# DC_DC.net
KiCad netlist of a schematic drawn in Altium Designer
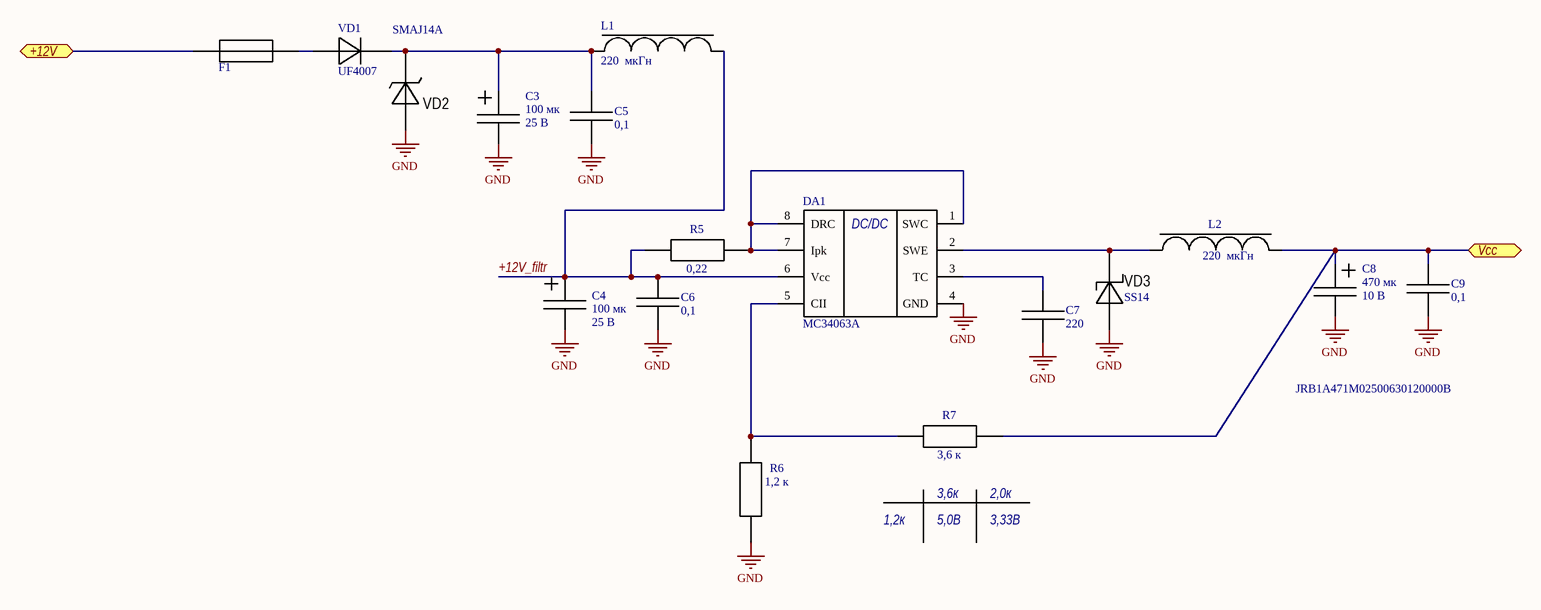
[diagram p0: DC_DC.SchDoc]

(export (version "E")
  (design (tool "Eeschema 10.0.6"))
  (components
    (comp (ref "C3")
      (value "~")
      (footprint "K50-35_6.3mm")
      (fields
        (field (name "PART NUMBER") "Конденсатор электролит. K50-35 100 мкФ 25 В +/- 20% JRB1E101M02500630110000B \"JB\"")
        (field (name "MANUFACTURER") "\"JB\"")
        (field (name "MANUFACTURERPARTNUMBER") "JRB1E101M02500630110000B")
        (field (name "POWER/VOLTAGE") "25 В")
        (field (name "VALUE SCH") "100 мк")
      )
      (libsource (lib "Library") (part "Конденсаторы электролитические"))
    )
    (comp (ref "C4")
      (value "~")
      (footprint "K50-35_6.3mm")
      (fields
        (field (name "PART NUMBER") "Конденсатор электролит. K50-35 100 мкФ 25 В +/- 20% JRB1E101M02500630110000B \"JB\"")
        (field (name "MANUFACTURER") "\"JB\"")
        (field (name "MANUFACTURERPARTNUMBER") "JRB1E101M02500630110000B")
        (field (name "POWER/VOLTAGE") "25 В")
        (field (name "VALUE SCH") "100 мк")
      )
      (libsource (lib "Library") (part "Конденсаторы электролитические"))
    )
    (comp (ref "C5")
      (value "Конденсаторы керамические")
      (footprint "C0603_autoMount")
      (fields
        (field (name "PART NUMBER") "Чип. керам. 0603 0,1 мкФ 50 В +/-10% X7R CC0603KKX7R9BB104 \"Yageo\"")
        (field (name "MANUFACTURER") "\"Yageo\"")
        (field (name "MANUFACTURERPARTNUMBER") "CC0603KKX7R9BB104")
        (field (name "VALUE SCH") "0,1")
      )
      (libsource (lib "Library") (part "Конденсаторы керамические"))
    )
    (comp (ref "C6")
      (value "Конденсаторы керамические")
      (footprint "C0603_autoMount")
      (fields
        (field (name "PART NUMBER") "Чип. керам. 0603 0,1 мкФ 50 В +/-10% X7R CC0603KKX7R9BB104 \"Yageo\"")
        (field (name "MANUFACTURER") "\"Yageo\"")
        (field (name "MANUFACTURERPARTNUMBER") "CC0603KKX7R9BB104")
        (field (name "VALUE SCH") "0,1")
      )
      (libsource (lib "Library") (part "Конденсаторы керамические"))
    )
    (comp (ref "C7")
      (value "Конденсаторы керамические")
      (footprint "C0603_autoMount")
      (fields
        (field (name "PART NUMBER") "Чип. керам. 0603 220 пФ 50 В +/-5% NP0 GRM1885C1H221J \"Murata\"")
        (field (name "MANUFACTURER") "\"Murata\"")
        (field (name "MANUFACTURERPARTNUMBER") "GRM1885C1H221J")
        (field (name "VALUE SCH") "220")
      )
      (libsource (lib "Library") (part "Конденсаторы керамические"))
    )
    (comp (ref "C8")
      (value "Конденсаторы электролитические")
      (footprint "K50-35_8mm")
      (fields
        (field (name "PART NUMBER") "Конденсатор электролит. К50-35 470 мкФ 10 В +/- 20% JRK1A471M03500800070000B")
        (field (name "MANUFACTURERPARTNUMBER") "JRK1A471M03500800070000B")
        (field (name "POWER/VOLTAGE") "10 В")
        (field (name "TOLERANCE") "+/- 20%")
        (field (name "VALUE SCH") "470 мк")
      )
      (libsource (lib "Library") (part "Конденсаторы электролитические"))
    )
    (comp (ref "C9")
      (value "Конденсаторы керамические")
      (footprint "C0603_autoMount")
      (fields
        (field (name "PART NUMBER") "Чип. керам. 0603 0,1 мкФ 50 В +/-10% X7R CC0603KKX7R9BB104 \"Yageo\"")
        (field (name "MANUFACTURER") "\"Yageo\"")
        (field (name "MANUFACTURERPARTNUMBER") "CC0603KKX7R9BB104")
        (field (name "VALUE SCH") "0,1")
      )
      (libsource (lib "Library") (part "Конденсаторы керамические"))
    )
    (comp (ref "DA1")
      (value "MC34063A")
      (footprint "SO-8")
      (fields
        (field (name "MANUFACTURER") "\"ST Microelectronix\"")
        (field (name "MANUFACTURERPARTNUMBER") "MC34063EC")
        (field (name "PART NUMBER") "Микросхема MC34063EC \"ST Microelectronix\" SO-8")
      )
      (libsource (lib "Library") (part "MC34063A"))
    )
    (comp (ref "F1")
      (value "Fuse")
      (footprint "R1812")
      (fields
        (field (name "PART NUMBER") "Предохранитель   0,2 A, 30 В 1812L020PR \"Littelfuse\"")
        (field (name "MANUFACTURER") "\"Littelfuse\"")
        (field (name "MANUFACTURERPARTNUMBER") "1812L020PR")
      )
      (libsource (lib "Library") (part "Fuse"))
    )
    (comp (ref "L1")
      (value "220  мкГн")
      (footprint "SDR0604")
      (fields
        (field (name "MANUFACTURER") "\"Bourns\"")
        (field (name "MANUFACTURERPARTNUMBER") "SDR0604-221KL")
        (field (name "TOLERANCE") "+/-20%")
      )
      (libsource (lib "Library") (part "Drossel"))
    )
    (comp (ref "L2")
      (value "220  мкГн")
      (footprint "SDR0604")
      (fields
        (field (name "MANUFACTURER") "\"Bourns\"")
        (field (name "MANUFACTURERPARTNUMBER") "SDR0604-221KL")
        (field (name "TOLERANCE") "+/-20%")
      )
      (libsource (lib "Library") (part "Drossel"))
    )
    (comp (ref "R5")
      (value "Resistor")
      (footprint "R1206_autoMount")
      (fields
        (field (name "PART NUMBER") "Чип рез. 1206 0,22 Ом  +/-1% RC1206FR-070R22L \"Yageo\"")
        (field (name "MANUFACTURER") "\"Yageo\"")
        (field (name "MANUFACTURERPARTNUMBER") "RC1206FR-070R22L")
        (field (name "VALUE SCH") "0,22")
      )
      (libsource (lib "Library") (part "Resistor"))
    )
    (comp (ref "R6")
      (value "Resistor")
      (footprint "R0603_autoMount")
      (fields
        (field (name "PART NUMBER") "Чип рез. 0603 1,2 кОм  +/-1% RC0603FR-071K2L \"Yageo\"")
        (field (name "MANUFACTURER") "\"Yageo\"")
        (field (name "MANUFACTURERPARTNUMBER") "RC0603FR-071K2L")
        (field (name "VALUE SСH") "1,2 к")
      )
      (libsource (lib "Library") (part "Resistor"))
    )
    (comp (ref "R7")
      (value "Resistor")
      (footprint "R0603_autoMount")
      (fields
        (field (name "PART NUMBER") "Чип рез. 0603 3,6 кОм  +/-1% RC0603FR-073K6L \"Yageo\"")
        (field (name "MANUFACTURER") "\"Yageo\"")
        (field (name "MANUFACTURERPARTNUMBER") "RC0603FR-073K6L")
        (field (name "VALUE SСH") "3,6 к")
      )
      (libsource (lib "") (part "Resistor_1"))
    )
    (comp (ref "VD1")
      (value "Diode")
      (footprint "DO-41_H_10mm")
      (fields
        (field (name "PART NUMBER") "Диод UF4007 \"ST Microelectronics\" DO-41")
        (field (name "MANUFACTURER") "\"ST Microelectronics\"")
        (field (name "MANUFACTURERPARTNUMBER") "UF4007")
      )
      (libsource (lib "Library") (part "Diode"))
    )
    (comp (ref "VD2")
      (value "TVS")
      (footprint "DO-214AC SMA")
      (fields
        (field (name "PART NUMBER") "Диод SMAJ14A \"Littelfuse\" SMA/DO-214AC")
        (field (name "MANUFACTURER") "\"Littelfuse\"")
        (field (name "MANUFACTURERPARTNUMBER") "SMAJ14A")
      )
      (libsource (lib "Library") (part "TVS"))
    )
    (comp (ref "VD3")
      (value "Shottke")
      (footprint "DO-214AC_SMA")
      (fields
        (field (name "PART NUMBER") "Диод SS14 \"ON Semiconductor\" SMA/DO-214AC")
        (field (name "MANUFACTURER") "\"ON Semiconductor\"")
        (field (name "MANUFACTURERPARTNUMBER") "SS14")
      )
      (libsource (lib "Library") (part "Shottke"))
    )
  )
  (nets
    (net (code "1") (name "/+12V") (class "Default")
      (node (ref "F1") (pin "2") (pinfunction "2_2") (pintype "passive"))
    )
    (net (code "2") (name "/+12V_filtr") (class "Default")
      (node (ref "C4") (pin "1") (pinfunction "1_1") (pintype "passive"))
      (node (ref "C6") (pin "2") (pinfunction "2_2") (pintype "passive"))
      (node (ref "DA1") (pin "6") (pinfunction "Vcc_6") (pintype "passive"))
      (node (ref "L1") (pin "1") (pinfunction "1_1") (pintype "passive"))
      (node (ref "R5") (pin "2") (pinfunction "2_2") (pintype "passive"))
    )
    (net (code "3") (name "/Vcc") (class "Default")
      (node (ref "C8") (pin "1") (pinfunction "1_1") (pintype "passive"))
      (node (ref "C9") (pin "2") (pinfunction "2_2") (pintype "passive"))
      (node (ref "L2") (pin "1") (pinfunction "1_1") (pintype "passive"))
      (node (ref "R7") (pin "2") (pinfunction "2_2") (pintype "passive"))
    )
    (net (code "4") (name "GND") (class "Default")
      (node (ref "C3") (pin "2") (pinfunction "2_2") (pintype "passive"))
      (node (ref "C4") (pin "2") (pinfunction "2_2") (pintype "passive"))
      (node (ref "C5") (pin "1") (pinfunction "1_1") (pintype "passive"))
      (node (ref "C6") (pin "1") (pinfunction "1_1") (pintype "passive"))
      (node (ref "C7") (pin "1") (pinfunction "1_1") (pintype "passive"))
      (node (ref "C8") (pin "2") (pinfunction "2_2") (pintype "passive"))
      (node (ref "C9") (pin "1") (pinfunction "1_1") (pintype "passive"))
      (node (ref "DA1") (pin "4") (pinfunction "GND_4") (pintype "passive"))
      (node (ref "R6") (pin "2") (pinfunction "2_2") (pintype "passive"))
      (node (ref "VD2") (pin "2") (pinfunction "2_2") (pintype "passive"))
      (node (ref "VD3") (pin "2") (pinfunction "2_2") (pintype "passive"))
    )
    (net (code "5") (name "Net-(C3-Pad1)") (class "Default")
      (node (ref "C3") (pin "1") (pinfunction "1_1") (pintype "passive"))
      (node (ref "C5") (pin "2") (pinfunction "2_2") (pintype "passive"))
      (node (ref "L1") (pin "2") (pinfunction "2_2") (pintype "passive"))
      (node (ref "VD1") (pin "1") (pinfunction "1_1") (pintype "passive"))
      (node (ref "VD2") (pin "1") (pinfunction "1_1") (pintype "passive"))
    )
    (net (code "6") (name "Net-(DA1-CII)") (class "Default")
      (node (ref "DA1") (pin "5") (pinfunction "CII_5") (pintype "passive"))
      (node (ref "R6") (pin "1") (pinfunction "1_1") (pintype "passive"))
      (node (ref "R7") (pin "1") (pinfunction "1_1") (pintype "passive"))
    )
    (net (code "7") (name "Net-(DA1-DRC)") (class "Default")
      (node (ref "DA1") (pin "1") (pinfunction "SWC_1") (pintype "passive"))
      (node (ref "DA1") (pin "7") (pinfunction "Ipk_7") (pintype "passive"))
      (node (ref "DA1") (pin "8") (pinfunction "DRC_8") (pintype "passive"))
      (node (ref "R5") (pin "1") (pinfunction "1_1") (pintype "passive"))
    )
    (net (code "8") (name "Net-(DA1-SWE)") (class "Default")
      (node (ref "DA1") (pin "2") (pinfunction "SWE_2") (pintype "passive"))
      (node (ref "L2") (pin "2") (pinfunction "2_2") (pintype "passive"))
      (node (ref "VD3") (pin "1") (pinfunction "1_1") (pintype "passive"))
    )
    (net (code "9") (name "Net-(DA1-TC)") (class "Default")
      (node (ref "C7") (pin "2") (pinfunction "2_2") (pintype "passive"))
      (node (ref "DA1") (pin "3") (pinfunction "TC_3") (pintype "passive"))
    )
    (net (code "10") (name "Net-(F1-Pad1)") (class "Default")
      (node (ref "F1") (pin "1") (pinfunction "1_1") (pintype "passive"))
      (node (ref "VD1") (pin "2") (pinfunction "2_2") (pintype "passive"))
    )
  )
)
